# 1_P1_schdoc.net
KiCad netlist of a schematic drawn in Altium Designer
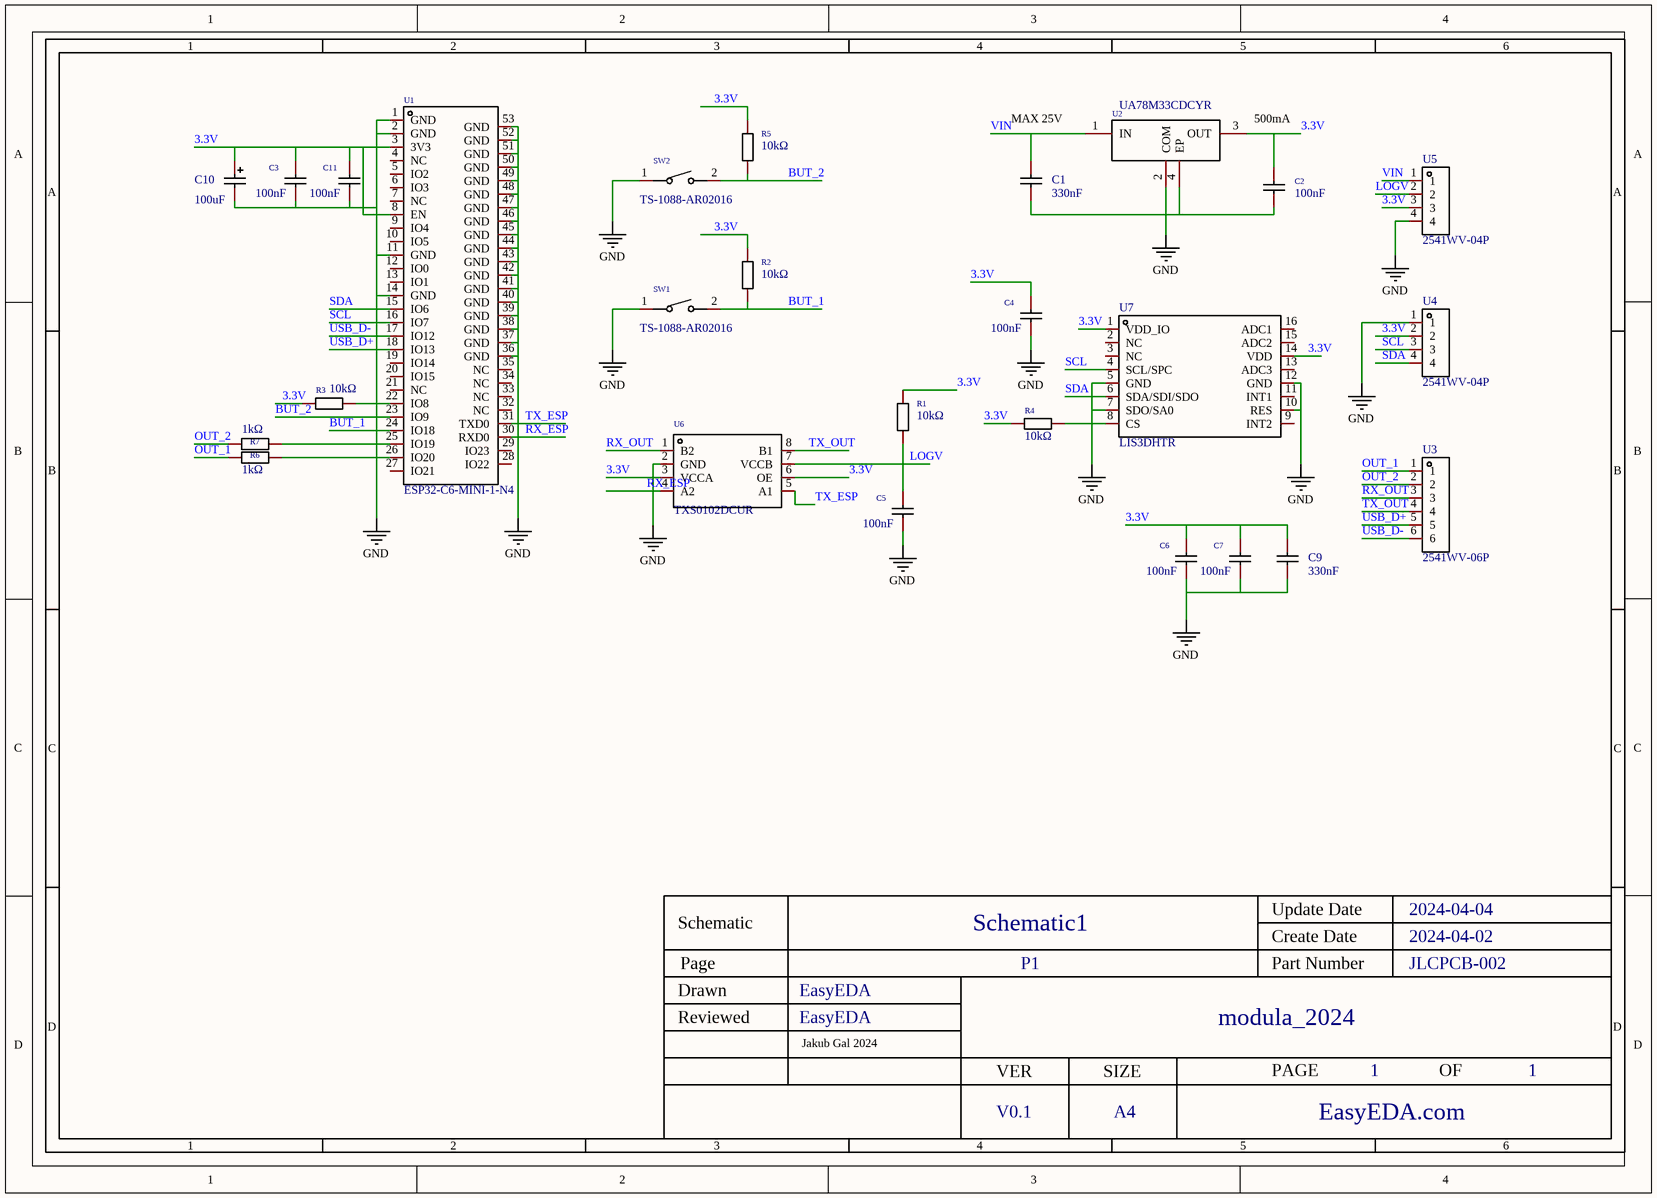
[diagram p0: 1_P1.schdoc.schdoc]

(export (version "E")
  (design (tool "Eeschema 10.0.6"))
  (components
    (comp (ref "C1")
      (value "330nF")
      (fields
        (field (name "NAME") "330nF")
        (field (name "MANUFACTURER") "FH(风华)")
        (field (name "MANUFACTURER PART") "0805B334K500NT")
        (field (name "TOLERANCE") "±10%")
      )
      (libsource (lib "altium-import") (part "root_1_0805B334K500NT_"))
    )
    (comp (ref "C2")
      (value "100nF")
      (fields
        (field (name "NAME") "100nF")
        (field (name "MANUFACTURER") "FH(风华)")
        (field (name "MANUFACTURER PART") "0603B104K500NT")
        (field (name "TOLERANCE") "±10%")
      )
      (libsource (lib "altium-import") (part "root_1_0603B104K500NT_C30926_"))
    )
    (comp (ref "C3")
      (value "100nF")
      (fields
        (field (name "NAME") "100nF")
        (field (name "MANUFACTURER") "FH(风华)")
        (field (name "MANUFACTURER PART") "0603B104K500NT")
        (field (name "TOLERANCE") "±10%")
      )
      (libsource (lib "altium-import") (part "root_1_0603B104K500NT_C30926_"))
    )
    (comp (ref "C4")
      (value "100nF")
      (fields
        (field (name "NAME") "100nF")
        (field (name "MANUFACTURER") "FH(风华)")
        (field (name "MANUFACTURER PART") "0603B104K500NT")
        (field (name "TOLERANCE") "±10%")
      )
      (libsource (lib "altium-import") (part "root_1_0603B104K500NT_C30926_"))
    )
    (comp (ref "C5")
      (value "100nF")
      (fields
        (field (name "NAME") "100nF")
        (field (name "MANUFACTURER") "FH(风华)")
        (field (name "MANUFACTURER PART") "0603B104K500NT")
        (field (name "TOLERANCE") "±10%")
      )
      (libsource (lib "altium-import") (part "root_1_0603B104K500NT_C30926_"))
    )
    (comp (ref "C6")
      (value "100nF")
      (fields
        (field (name "NAME") "100nF")
        (field (name "MANUFACTURER") "FH(风华)")
        (field (name "MANUFACTURER PART") "0603B104K500NT")
        (field (name "TOLERANCE") "±10%")
      )
      (libsource (lib "altium-import") (part "root_1_0603B104K500NT_C30926_"))
    )
    (comp (ref "C7")
      (value "100nF")
      (fields
        (field (name "NAME") "100nF")
        (field (name "MANUFACTURER") "FH(风华)")
        (field (name "MANUFACTURER PART") "0603B104K500NT")
        (field (name "TOLERANCE") "±10%")
      )
      (libsource (lib "altium-import") (part "root_1_0603B104K500NT_C30926_"))
    )
    (comp (ref "C9")
      (value "330nF")
      (fields
        (field (name "NAME") "330nF")
        (field (name "MANUFACTURER") "FH(风华)")
        (field (name "MANUFACTURER PART") "0805B334K500NT")
        (field (name "TOLERANCE") "±10%")
      )
      (libsource (lib "altium-import") (part "root_1_0805B334K500NT_"))
    )
    (comp (ref "C10")
      (value "100uF")
      (fields
        (field (name "NAME") "100uF")
        (field (name "MANUFACTURER") "CEC(振华新云)")
        (field (name "MANUFACTURER PART") "CA45-B-6.3V-100uF-K")
        (field (name "TOLERANCE") "±10%")
      )
      (libsource (lib "altium-import") (part "root_1_CA45-B-6.3V-100uF-K_"))
    )
    (comp (ref "C11")
      (value "100nF")
      (fields
        (field (name "NAME") "100nF")
        (field (name "MANUFACTURER") "FH(风华)")
        (field (name "MANUFACTURER PART") "0603B104K500NT")
        (field (name "TOLERANCE") "±10%")
      )
      (libsource (lib "altium-import") (part "root_1_0603B104K500NT_C30926_"))
    )
    (comp (ref "R1")
      (value "10kΩ")
      (fields
        (field (name "NAME") "10kΩ")
        (field (name "MANUFACTURER") "UNI-ROYAL(厚声)")
        (field (name "MANUFACTURER PART") "0603WAF1002T5E")
        (field (name "TOLERANCE") "±1%")
      )
      (libsource (lib "altium-import") (part "root_1_0603WAF1002T5E_"))
    )
    (comp (ref "R2")
      (value "10kΩ")
      (fields
        (field (name "NAME") "10kΩ")
        (field (name "MANUFACTURER") "UNI-ROYAL(厚声)")
        (field (name "MANUFACTURER PART") "0603WAF1002T5E")
        (field (name "TOLERANCE") "±1%")
      )
      (libsource (lib "altium-import") (part "root_1_0603WAF1002T5E_"))
    )
    (comp (ref "R3")
      (value "10kΩ")
      (fields
        (field (name "NAME") "10kΩ")
        (field (name "MANUFACTURER") "UNI-ROYAL(厚声)")
        (field (name "MANUFACTURER PART") "0603WAF1002T5E")
        (field (name "TOLERANCE") "±1%")
      )
      (libsource (lib "altium-import") (part "root_2_0603WAF1002T5E_"))
    )
    (comp (ref "R4")
      (value "10kΩ")
      (fields
        (field (name "NAME") "10kΩ")
        (field (name "MANUFACTURER") "UNI-ROYAL(厚声)")
        (field (name "MANUFACTURER PART") "0603WAF1002T5E")
        (field (name "TOLERANCE") "±1%")
      )
      (libsource (lib "altium-import") (part "root_2_0603WAF1002T5E_"))
    )
    (comp (ref "R5")
      (value "10kΩ")
      (fields
        (field (name "NAME") "10kΩ")
        (field (name "MANUFACTURER") "UNI-ROYAL(厚声)")
        (field (name "MANUFACTURER PART") "0603WAF1002T5E")
        (field (name "TOLERANCE") "±1%")
      )
      (libsource (lib "altium-import") (part "root_1_0603WAF1002T5E_"))
    )
    (comp (ref "R6")
      (value "1kΩ")
      (fields
        (field (name "NAME") "1kΩ")
        (field (name "MANUFACTURER") "UNI-ROYAL(厚声)")
        (field (name "MANUFACTURER PART") "0603WAJ0102T5E")
        (field (name "TOLERANCE") "±5%")
      )
      (libsource (lib "altium-import") (part "root_0_0603WAJ0102T5E_"))
    )
    (comp (ref "R7")
      (value "1kΩ")
      (fields
        (field (name "NAME") "1kΩ")
        (field (name "MANUFACTURER") "UNI-ROYAL(厚声)")
        (field (name "MANUFACTURER PART") "0603WAJ0102T5E")
        (field (name "TOLERANCE") "±5%")
      )
      (libsource (lib "altium-import") (part "root_0_0603WAJ0102T5E_"))
    )
    (comp (ref "SW1")
      (value "TS-1088-AR02016")
      (fields (field (name "NAME") "TS-1088-AR02016") (field (name "MANUFACTURER") "XUNPU(讯普)"))
      (libsource (lib "altium-import") (part "root_0_TS-1088-AR02016_"))
    )
    (comp (ref "SW2")
      (value "TS-1088-AR02016")
      (fields (field (name "NAME") "TS-1088-AR02016") (field (name "MANUFACTURER") "XUNPU(讯普)"))
      (libsource (lib "altium-import") (part "root_0_TS-1088-AR02016_"))
    )
    (comp (ref "U1")
      (value "ESP32-C6-MINI-1-N4")
      (fields (field (name "NAME") "ESP32-C6-MINI-1-N4") (field (name "MANUFACTURER") "ESPRESSIF(乐鑫)"))
      (libsource (lib "altium-import") (part "root_0_ESP32-C6-MINI-1-N4_"))
    )
    (comp (ref "U2")
      (value "UA78M33CDCYR")
      (fields (field (name "NAME") "UA78M33CDCYR") (field (name "MANUFACTURER") "TI(德州仪器)"))
      (libsource (lib "altium-import") (part "root_0_UA78M33CDCYR_"))
    )
    (comp (ref "U3")
      (value "2541WV-06P")
      (fields (field (name "NAME") "2541WV-06P") (field (name "MANUFACTURER") "HanElectricity(瀚源)"))
      (libsource (lib "altium-import") (part "root_0_2541WV-06P_"))
    )
    (comp (ref "U4")
      (value "2541WV-04P")
      (fields (field (name "NAME") "2541WV-04P") (field (name "MANUFACTURER") "HanElectricity(瀚源)"))
      (libsource (lib "altium-import") (part "root_0_2541WV-04P_"))
    )
    (comp (ref "U5")
      (value "2541WV-04P")
      (fields (field (name "NAME") "2541WV-04P") (field (name "MANUFACTURER") "HanElectricity(瀚源)"))
      (libsource (lib "altium-import") (part "root_0_2541WV-04P_"))
    )
    (comp (ref "U6")
      (value "TXS0102DCUR")
      (fields (field (name "NAME") "TXS0102DCUR") (field (name "MANUFACTURER") "TI(德州仪器)"))
      (libsource (lib "altium-import") (part "root_0_TXS0102DCUR_"))
    )
    (comp (ref "U7")
      (value "LIS3DHTR")
      (fields (field (name "NAME") "LIS3DHTR") (field (name "MANUFACTURER") "ST(意法半导体)"))
      (libsource (lib "altium-import") (part "root_0_LIS3DHTR_"))
    )
  )
  (nets
    (net (code "1") (name "/3.3V") (class "Default")
      (node (ref "C10") (pin "1") (pinfunction "1_1") (pintype "passive"))
      (node (ref "C11") (pin "2") (pinfunction "2_2") (pintype "passive"))
      (node (ref "C2") (pin "2") (pinfunction "2_2") (pintype "passive"))
      (node (ref "C3") (pin "2") (pinfunction "2_2") (pintype "passive"))
      (node (ref "C4") (pin "2") (pinfunction "2_2") (pintype "passive"))
      (node (ref "C6") (pin "2") (pinfunction "2_2") (pintype "passive"))
      (node (ref "C7") (pin "2") (pinfunction "2_2") (pintype "passive"))
      (node (ref "C9") (pin "2") (pinfunction "2_2") (pintype "passive"))
      (node (ref "R1") (pin "2") (pinfunction "2_2") (pintype "passive"))
      (node (ref "R2") (pin "2") (pinfunction "2_2") (pintype "passive"))
      (node (ref "R3") (pin "2") (pinfunction "2_2") (pintype "passive"))
      (node (ref "R4") (pin "2") (pinfunction "2_2") (pintype "passive"))
      (node (ref "R5") (pin "2") (pinfunction "2_2") (pintype "passive"))
      (node (ref "U1") (pin "3") (pinfunction "3V3_3") (pintype "passive"))
      (node (ref "U1") (pin "8") (pinfunction "EN_8") (pintype "passive"))
      (node (ref "U2") (pin "3") (pinfunction "OUT_3") (pintype "passive"))
      (node (ref "U4") (pin "2") (pinfunction "2_2") (pintype "passive"))
      (node (ref "U5") (pin "3") (pinfunction "3_3") (pintype "passive"))
      (node (ref "U6") (pin "3") (pinfunction "VCCA_3") (pintype "passive"))
      (node (ref "U6") (pin "6") (pinfunction "OE_6") (pintype "passive"))
      (node (ref "U7") (pin "1") (pinfunction "VDD_IO_1") (pintype "passive"))
      (node (ref "U7") (pin "14") (pinfunction "VDD_14") (pintype "passive"))
    )
    (net (code "2") (name "/BUT_1") (class "Default")
      (node (ref "R2") (pin "1") (pinfunction "1_1") (pintype "passive"))
      (node (ref "SW1") (pin "2") (pinfunction "2_2") (pintype "passive"))
      (node (ref "U1") (pin "24") (pinfunction "IO18_24") (pintype "passive"))
    )
    (net (code "3") (name "/BUT_2") (class "Default")
      (node (ref "R5") (pin "1") (pinfunction "1_1") (pintype "passive"))
      (node (ref "SW2") (pin "2") (pinfunction "2_2") (pintype "passive"))
      (node (ref "U1") (pin "23") (pinfunction "IO9_23") (pintype "passive"))
    )
    (net (code "4") (name "/LOGV") (class "Default")
      (node (ref "C5") (pin "2") (pinfunction "2_2") (pintype "passive"))
      (node (ref "R1") (pin "1") (pinfunction "1_1") (pintype "passive"))
      (node (ref "U5") (pin "2") (pinfunction "2_2") (pintype "passive"))
      (node (ref "U6") (pin "7") (pinfunction "VCCB_7") (pintype "passive"))
    )
    (net (code "5") (name "/OUT_1") (class "Default")
      (node (ref "R6") (pin "1") (pinfunction "1_1") (pintype "passive"))
      (node (ref "U3") (pin "1") (pinfunction "1_1") (pintype "passive"))
    )
    (net (code "6") (name "/OUT_2") (class "Default")
      (node (ref "R7") (pin "1") (pinfunction "1_1") (pintype "passive"))
      (node (ref "U3") (pin "2") (pinfunction "2_2") (pintype "passive"))
    )
    (net (code "7") (name "/RX_ESP") (class "Default")
      (node (ref "U1") (pin "30") (pinfunction "RXD0_30") (pintype "passive"))
      (node (ref "U6") (pin "4") (pinfunction "A2_4") (pintype "passive"))
    )
    (net (code "8") (name "/RX_OUT") (class "Default")
      (node (ref "U3") (pin "3") (pinfunction "3_3") (pintype "passive"))
      (node (ref "U6") (pin "1") (pinfunction "B2_1") (pintype "passive"))
    )
    (net (code "9") (name "/SCL") (class "Default")
      (node (ref "U1") (pin "16") (pinfunction "IO7_16") (pintype "passive"))
      (node (ref "U4") (pin "3") (pinfunction "3_3") (pintype "passive"))
      (node (ref "U7") (pin "4") (pinfunction "SCL/SPC_4") (pintype "passive"))
    )
    (net (code "10") (name "/SDA") (class "Default")
      (node (ref "U1") (pin "15") (pinfunction "IO6_15") (pintype "passive"))
      (node (ref "U4") (pin "4") (pinfunction "4_4") (pintype "passive"))
      (node (ref "U7") (pin "6") (pinfunction "SDA/SDI/SDO_6") (pintype "passive"))
    )
    (net (code "11") (name "/TX_ESP") (class "Default")
      (node (ref "U1") (pin "31") (pinfunction "TXD0_31") (pintype "passive"))
      (node (ref "U6") (pin "5") (pinfunction "A1_5") (pintype "passive"))
    )
    (net (code "12") (name "/TX_OUT") (class "Default")
      (node (ref "U3") (pin "4") (pinfunction "4_4") (pintype "passive"))
      (node (ref "U6") (pin "8") (pinfunction "B1_8") (pintype "passive"))
    )
    (net (code "13") (name "/USB_D+") (class "Default")
      (node (ref "U1") (pin "18") (pinfunction "IO13_18") (pintype "passive"))
      (node (ref "U3") (pin "5") (pinfunction "5_5") (pintype "passive"))
    )
    (net (code "14") (name "/USB_D-") (class "Default")
      (node (ref "U1") (pin "17") (pinfunction "IO12_17") (pintype "passive"))
      (node (ref "U3") (pin "6") (pinfunction "6_6") (pintype "passive"))
    )
    (net (code "15") (name "/VIN") (class "Default")
      (node (ref "C1") (pin "2") (pinfunction "2_2") (pintype "passive"))
      (node (ref "U2") (pin "1") (pinfunction "IN_1") (pintype "passive"))
      (node (ref "U5") (pin "1") (pinfunction "1_1") (pintype "passive"))
    )
    (net (code "16") (name "GND") (class "Default")
      (node (ref "C1") (pin "1") (pinfunction "1_1") (pintype "passive"))
      (node (ref "C10") (pin "2") (pinfunction "2_2") (pintype "passive"))
      (node (ref "C11") (pin "1") (pinfunction "1_1") (pintype "passive"))
      (node (ref "C2") (pin "1") (pinfunction "1_1") (pintype "passive"))
      (node (ref "C3") (pin "1") (pinfunction "1_1") (pintype "passive"))
      (node (ref "C4") (pin "1") (pinfunction "1_1") (pintype "passive"))
      (node (ref "C5") (pin "1") (pinfunction "1_1") (pintype "passive"))
      (node (ref "C6") (pin "1") (pinfunction "1_1") (pintype "passive"))
      (node (ref "C7") (pin "1") (pinfunction "1_1") (pintype "passive"))
      (node (ref "C9") (pin "1") (pinfunction "1_1") (pintype "passive"))
      (node (ref "SW1") (pin "1") (pinfunction "1_1") (pintype "passive"))
      (node (ref "SW2") (pin "1") (pinfunction "1_1") (pintype "passive"))
      (node (ref "U1") (pin "1") (pinfunction "GND_1") (pintype "passive"))
      (node (ref "U1") (pin "11") (pinfunction "GND_11") (pintype "passive"))
      (node (ref "U1") (pin "14") (pinfunction "GND_14") (pintype "passive"))
      (node (ref "U1") (pin "2") (pinfunction "GND_2") (pintype "passive"))
      (node (ref "U1") (pin "36") (pinfunction "GND_36") (pintype "passive"))
      (node (ref "U1") (pin "37") (pinfunction "GND_37") (pintype "passive"))
      (node (ref "U1") (pin "38") (pinfunction "GND_38") (pintype "passive"))
      (node (ref "U1") (pin "39") (pinfunction "GND_39") (pintype "passive"))
      (node (ref "U1") (pin "40") (pinfunction "GND_40") (pintype "passive"))
      (node (ref "U1") (pin "41") (pinfunction "GND_41") (pintype "passive"))
      (node (ref "U1") (pin "42") (pinfunction "GND_42") (pintype "passive"))
      (node (ref "U1") (pin "43") (pinfunction "GND_43") (pintype "passive"))
      (node (ref "U1") (pin "44") (pinfunction "GND_44") (pintype "passive"))
      (node (ref "U1") (pin "45") (pinfunction "GND_45") (pintype "passive"))
      (node (ref "U1") (pin "46") (pinfunction "GND_46") (pintype "passive"))
      (node (ref "U1") (pin "47") (pinfunction "GND_47") (pintype "passive"))
      (node (ref "U1") (pin "48") (pinfunction "GND_48") (pintype "passive"))
      (node (ref "U1") (pin "49") (pinfunction "GND_49") (pintype "passive"))
      (node (ref "U1") (pin "50") (pinfunction "GND_50") (pintype "passive"))
      (node (ref "U1") (pin "51") (pinfunction "GND_51") (pintype "passive"))
      (node (ref "U1") (pin "52") (pinfunction "GND_52") (pintype "passive"))
      (node (ref "U1") (pin "53") (pinfunction "GND_53") (pintype "passive"))
      (node (ref "U2") (pin "2") (pinfunction "COM_2") (pintype "passive"))
      (node (ref "U2") (pin "4") (pinfunction "EP_4") (pintype "passive"))
      (node (ref "U4") (pin "1") (pinfunction "1_1") (pintype "passive"))
      (node (ref "U5") (pin "4") (pinfunction "4_4") (pintype "passive"))
      (node (ref "U6") (pin "2") (pinfunction "GND_2") (pintype "passive"))
      (node (ref "U7") (pin "10") (pinfunction "RES_10") (pintype "passive"))
      (node (ref "U7") (pin "12") (pinfunction "GND_12") (pintype "passive"))
      (node (ref "U7") (pin "5") (pinfunction "GND_5") (pintype "passive"))
      (node (ref "U7") (pin "7") (pinfunction "SDO/SA0_7") (pintype "passive"))
    )
    (net (code "17") (name "Net-(U1-IO8)") (class "Default")
      (node (ref "R3") (pin "1") (pinfunction "1_1") (pintype "passive"))
      (node (ref "U1") (pin "22") (pinfunction "IO8_22") (pintype "passive"))
    )
    (net (code "18") (name "Net-(U1-IO19)") (class "Default")
      (node (ref "R7") (pin "2") (pinfunction "2_2") (pintype "passive"))
      (node (ref "U1") (pin "25") (pinfunction "IO19_25") (pintype "passive"))
    )
    (net (code "19") (name "Net-(U1-IO20)") (class "Default")
      (node (ref "R6") (pin "2") (pinfunction "2_2") (pintype "passive"))
      (node (ref "U1") (pin "26") (pinfunction "IO20_26") (pintype "passive"))
    )
    (net (code "20") (name "Net-(U7-CS)") (class "Default")
      (node (ref "R4") (pin "1") (pinfunction "1_1") (pintype "passive"))
      (node (ref "U7") (pin "8") (pinfunction "CS_8") (pintype "passive"))
    )
    (net (code "21") (name "unconnected-(U1-IO0-Pad12)") (class "Default")
      (node (ref "U1") (pin "12") (pinfunction "IO0_12") (pintype "passive"))
    )
    (net (code "22") (name "unconnected-(U1-IO1-Pad13)") (class "Default")
      (node (ref "U1") (pin "13") (pinfunction "IO1_13") (pintype "passive"))
    )
    (net (code "23") (name "unconnected-(U1-IO2-Pad5)") (class "Default")
      (node (ref "U1") (pin "5") (pinfunction "IO2_5") (pintype "passive"))
    )
    (net (code "24") (name "unconnected-(U1-IO3-Pad6)") (class "Default")
      (node (ref "U1") (pin "6") (pinfunction "IO3_6") (pintype "passive"))
    )
    (net (code "25") (name "unconnected-(U1-IO4-Pad9)") (class "Default")
      (node (ref "U1") (pin "9") (pinfunction "IO4_9") (pintype "passive"))
    )
    (net (code "26") (name "unconnected-(U1-IO5-Pad10)") (class "Default")
      (node (ref "U1") (pin "10") (pinfunction "IO5_10") (pintype "passive"))
    )
    (net (code "27") (name "unconnected-(U1-IO14-Pad19)") (class "Default")
      (node (ref "U1") (pin "19") (pinfunction "IO14_19") (pintype "passive"))
    )
    (net (code "28") (name "unconnected-(U1-IO15-Pad20)") (class "Default")
      (node (ref "U1") (pin "20") (pinfunction "IO15_20") (pintype "passive"))
    )
    (net (code "29") (name "unconnected-(U1-IO21-Pad27)") (class "Default")
      (node (ref "U1") (pin "27") (pinfunction "IO21_27") (pintype "passive"))
    )
    (net (code "30") (name "unconnected-(U1-IO22-Pad28)") (class "Default")
      (node (ref "U1") (pin "28") (pinfunction "IO22_28") (pintype "passive"))
    )
    (net (code "31") (name "unconnected-(U1-IO23-Pad29)") (class "Default")
      (node (ref "U1") (pin "29") (pinfunction "IO23_29") (pintype "passive"))
    )
    (net (code "32") (name "unconnected-(U1-NC-Pad4)") (class "Default")
      (node (ref "U1") (pin "4") (pinfunction "NC_4") (pintype "passive"))
    )
    (net (code "33") (name "unconnected-(U1-NC-Pad7)") (class "Default")
      (node (ref "U1") (pin "7") (pinfunction "NC_7") (pintype "passive"))
    )
    (net (code "34") (name "unconnected-(U1-NC-Pad21)") (class "Default")
      (node (ref "U1") (pin "21") (pinfunction "NC_21") (pintype "passive"))
    )
    (net (code "35") (name "unconnected-(U1-NC-Pad32)") (class "Default")
      (node (ref "U1") (pin "32") (pinfunction "NC_32") (pintype "passive"))
    )
    (net (code "36") (name "unconnected-(U1-NC-Pad33)") (class "Default")
      (node (ref "U1") (pin "33") (pinfunction "NC_33") (pintype "passive"))
    )
    (net (code "37") (name "unconnected-(U1-NC-Pad34)") (class "Default")
      (node (ref "U1") (pin "34") (pinfunction "NC_34") (pintype "passive"))
    )
    (net (code "38") (name "unconnected-(U1-NC-Pad35)") (class "Default")
      (node (ref "U1") (pin "35") (pinfunction "NC_35") (pintype "passive"))
    )
    (net (code "39") (name "unconnected-(U7-ADC1-Pad16)") (class "Default")
      (node (ref "U7") (pin "16") (pinfunction "ADC1_16") (pintype "passive"))
    )
    (net (code "40") (name "unconnected-(U7-ADC2-Pad15)") (class "Default")
      (node (ref "U7") (pin "15") (pinfunction "ADC2_15") (pintype "passive"))
    )
    (net (code "41") (name "unconnected-(U7-ADC3-Pad13)") (class "Default")
      (node (ref "U7") (pin "13") (pinfunction "ADC3_13") (pintype "passive"))
    )
    (net (code "42") (name "unconnected-(U7-INT1-Pad11)") (class "Default")
      (node (ref "U7") (pin "11") (pinfunction "INT1_11") (pintype "passive"))
    )
    (net (code "43") (name "unconnected-(U7-INT2-Pad9)") (class "Default")
      (node (ref "U7") (pin "9") (pinfunction "INT2_9") (pintype "passive"))
    )
    (net (code "44") (name "unconnected-(U7-NC-Pad2)") (class "Default")
      (node (ref "U7") (pin "2") (pinfunction "NC_2") (pintype "passive"))
    )
    (net (code "45") (name "unconnected-(U7-NC-Pad3)") (class "Default")
      (node (ref "U7") (pin "3") (pinfunction "NC_3") (pintype "passive"))
    )
  )
)
